# schaltplan.net
KiCad netlist of a schematic drawn in EAGLE
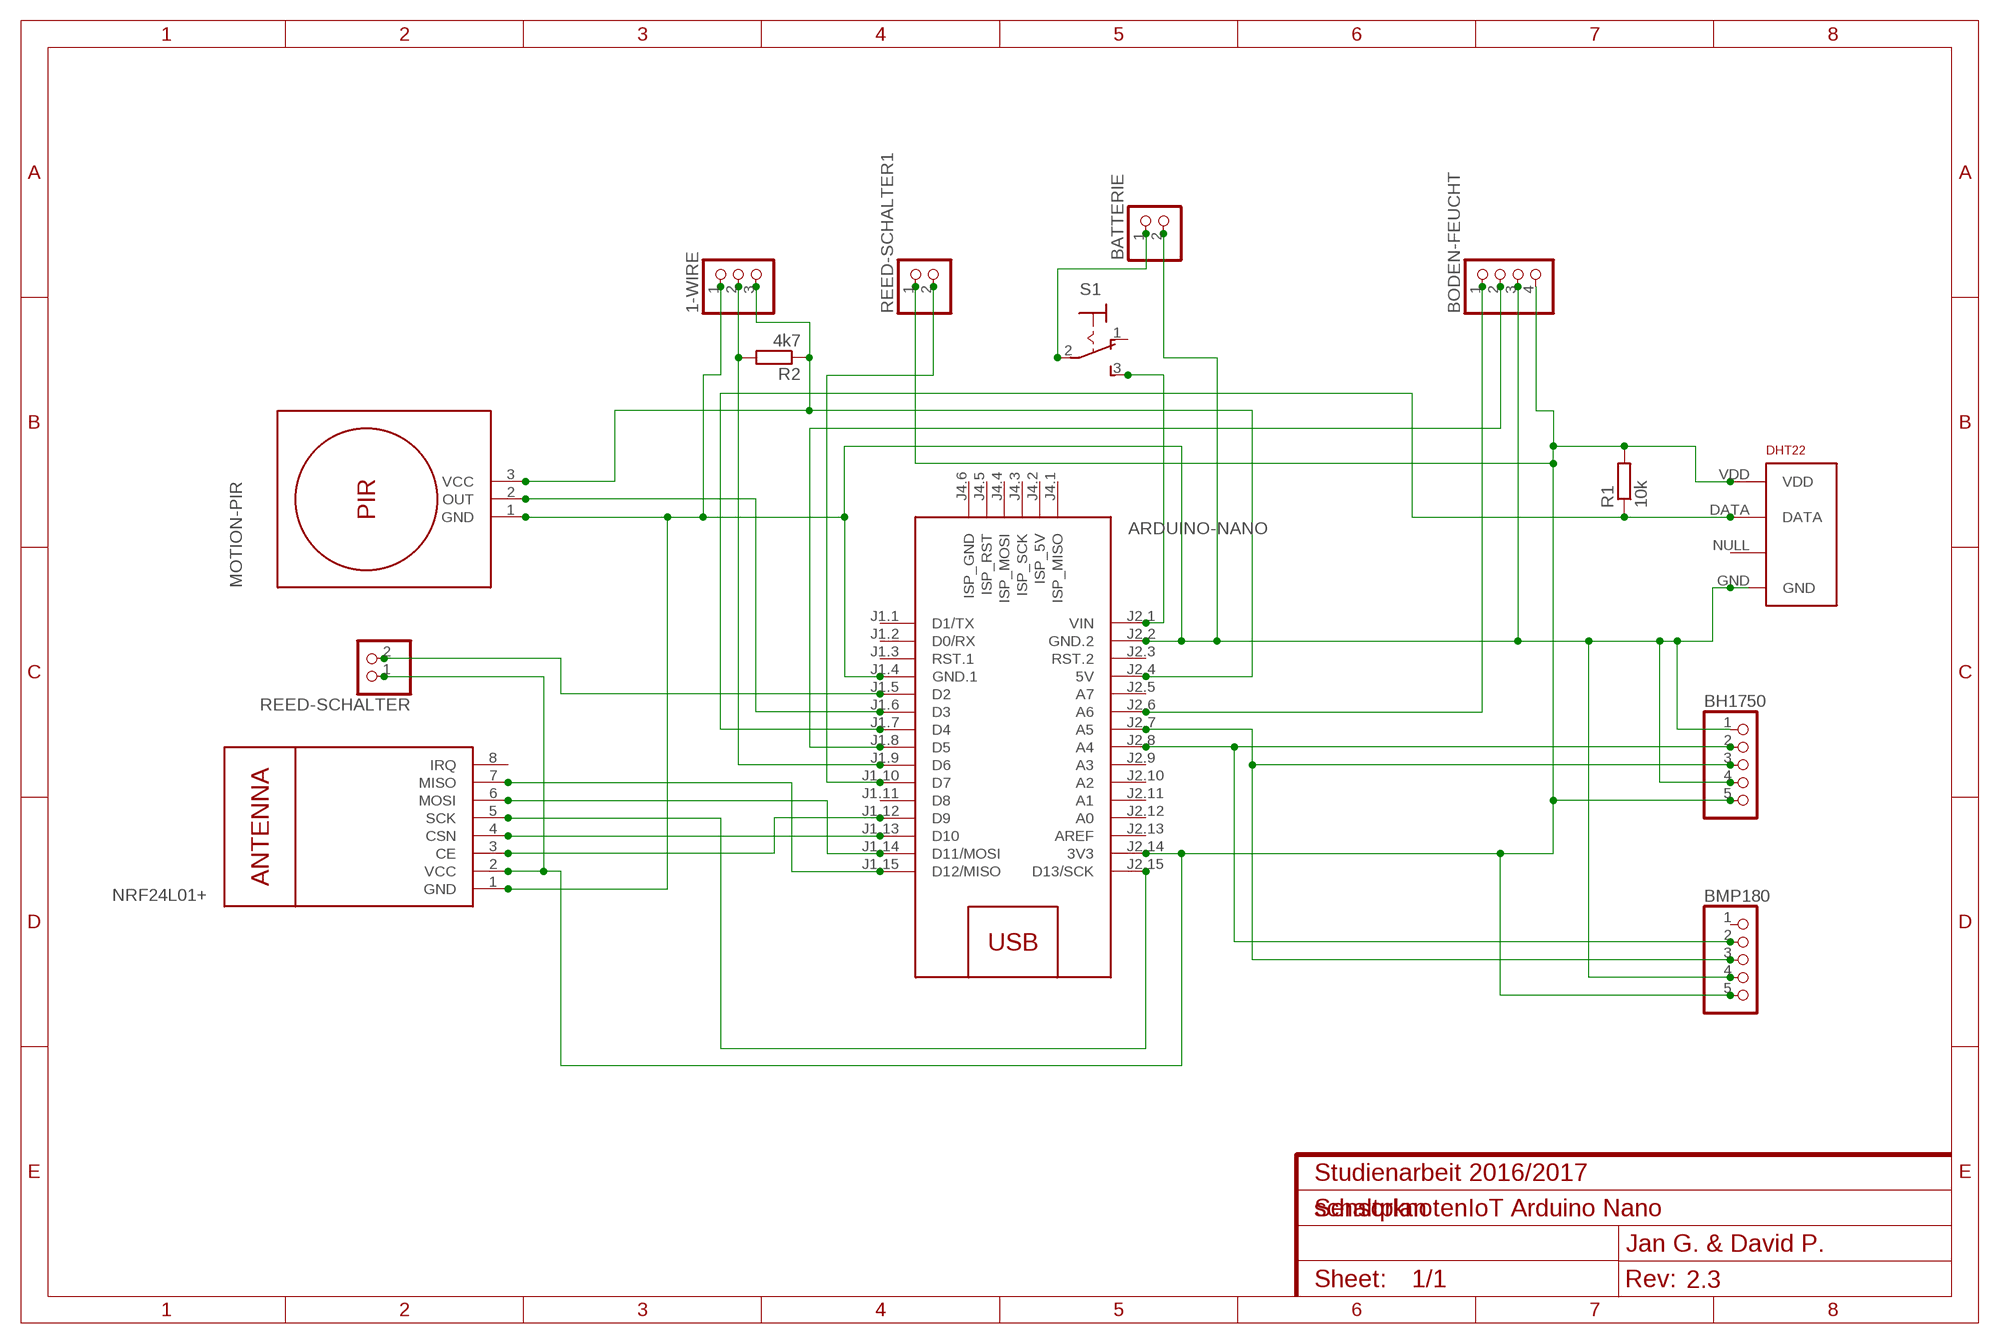
[diagram p0: schematic, sheet 1]

(export (version "E")
  (design (tool "Eeschema 10.0.6"))
  (components
    (comp (ref "1-WIRE")
      (value "PINHD-1X3")
      (footprint "eagle-import:1X03")
      (libsource (lib "eagle-import") (part "PINHD-1X3"))
    )
    (comp (ref "ARDUINO-NANO")
      (value "ARDUINO-NANO-3.0#ISP")
      (footprint "eagle-import:ARDUINO-NANO-3.0#ISP")
      (libsource (lib "eagle-import") (part "ARDUINO-NANO-3.0#ISP"))
    )
    (comp (ref "BATTERIE")
      (value "PINHD-1X2")
      (footprint "eagle-import:1X02")
      (libsource (lib "eagle-import") (part "PINHD-1X2"))
    )
    (comp (ref "BH1750")
      (value "PINHD-1X5")
      (footprint "eagle-import:1X05")
      (libsource (lib "eagle-import") (part "PINHD-1X5"))
    )
    (comp (ref "BMP180")
      (value "PINHD-1X5")
      (footprint "eagle-import:1X05")
      (libsource (lib "eagle-import") (part "PINHD-1X5"))
    )
    (comp (ref "BODEN-FEUCHT")
      (value "PINHD-1X4")
      (footprint "eagle-import:1X04")
      (libsource (lib "eagle-import") (part "PINHD-1X4"))
    )
    (comp (ref "DHT22")
      (value "RHT03_DHT-22_AM2302")
      (footprint "eagle-import:RHT03_DHT-22")
      (libsource (lib "eagle-import") (part "RHT03_DHT-22_AM2302"))
    )
    (comp (ref "MOTION-PIR")
      (value "MOTION-PIR-DYP-ME003")
      (footprint "eagle-import:MOTION-PIR-DYP-ME003")
      (libsource (lib "eagle-import") (part "MOTION-PIR-DYP-ME003"))
    )
    (comp (ref "NRF24L01+")
      (value "WIRELESS-NRF24L01")
      (footprint "eagle-import:WIRELESS-NRF24L01")
      (libsource (lib "eagle-import") (part "WIRELESS-NRF24L01"))
    )
    (comp (ref "R1")
      (value "10k")
      (footprint "eagle-import:0207_10")
      (libsource (lib "eagle-import") (part "R-EU_0207/10"))
    )
    (comp (ref "R2")
      (value "4k7")
      (footprint "eagle-import:0207_10")
      (libsource (lib "eagle-import") (part "R-EU_0207/10"))
    )
    (comp (ref "REED-SCHALTER")
      (value "PINHD-1X2")
      (footprint "eagle-import:1X02")
      (libsource (lib "eagle-import") (part "PINHD-1X2"))
    )
    (comp (ref "REED-SCHALTER1")
      (value "PINHD-1X2")
      (footprint "eagle-import:1X02")
      (libsource (lib "eagle-import") (part "PINHD-1X2"))
    )
    (comp (ref "S1")
      (value "320-916")
      (footprint "eagle-import:320-916")
      (libsource (lib "eagle-import") (part "320-916"))
    )
  )
  (nets
    (net (code "1") (name "Net-(ARDUINO-NANO-3V3)") (class "Default")
      (node (ref "ARDUINO-NANO") (pin "J2.14") (pinfunction "3V3_J2.14") (pintype "power_in"))
      (node (ref "BH1750") (pin "5") (pinfunction "5_5") (pintype "passive"))
      (node (ref "BMP180") (pin "5") (pinfunction "5_5") (pintype "passive"))
      (node (ref "BODEN-FEUCHT") (pin "4") (pinfunction "4_4") (pintype "passive"))
      (node (ref "DHT22") (pin "VDD") (pinfunction "VDD_VDD") (pintype "power_in"))
      (node (ref "NRF24L01+") (pin "2") (pinfunction "VCC_2") (pintype "power_in"))
      (node (ref "R1") (pin "2") (pinfunction "2_2") (pintype "passive"))
      (node (ref "REED-SCHALTER") (pin "1") (pinfunction "1_1") (pintype "passive"))
      (node (ref "REED-SCHALTER1") (pin "1") (pinfunction "1_1") (pintype "passive"))
    )
    (net (code "2") (name "Net-(ARDUINO-NANO-5V)") (class "Default")
      (node (ref "1-WIRE") (pin "3") (pinfunction "3_3") (pintype "passive"))
      (node (ref "ARDUINO-NANO") (pin "J2.4") (pinfunction "5V_J2.4") (pintype "power_in"))
      (node (ref "MOTION-PIR") (pin "3") (pinfunction "VCC_3") (pintype "power_in"))
      (node (ref "R2") (pin "1") (pinfunction "1_1") (pintype "passive"))
    )
    (net (code "3") (name "Net-(ARDUINO-NANO-A4)") (class "Default")
      (node (ref "ARDUINO-NANO") (pin "J2.8") (pinfunction "A4_J2.8") (pintype "bidirectional"))
      (node (ref "BH1750") (pin "2") (pinfunction "2_2") (pintype "passive"))
      (node (ref "BMP180") (pin "2") (pinfunction "2_2") (pintype "passive"))
    )
    (net (code "4") (name "Net-(ARDUINO-NANO-A5)") (class "Default")
      (node (ref "ARDUINO-NANO") (pin "J2.7") (pinfunction "A5_J2.7") (pintype "bidirectional"))
      (node (ref "BH1750") (pin "3") (pinfunction "3_3") (pintype "passive"))
      (node (ref "BMP180") (pin "3") (pinfunction "3_3") (pintype "passive"))
    )
    (net (code "5") (name "Net-(ARDUINO-NANO-A6)") (class "Default")
      (node (ref "ARDUINO-NANO") (pin "J2.6") (pinfunction "A6_J2.6") (pintype "bidirectional"))
      (node (ref "BODEN-FEUCHT") (pin "1") (pinfunction "1_1") (pintype "passive"))
    )
    (net (code "6") (name "Net-(ARDUINO-NANO-D2)") (class "Default")
      (node (ref "ARDUINO-NANO") (pin "J1.5") (pinfunction "D2_J1.5") (pintype "bidirectional"))
      (node (ref "REED-SCHALTER") (pin "2") (pinfunction "2_2") (pintype "passive"))
    )
    (net (code "7") (name "Net-(ARDUINO-NANO-D3)") (class "Default")
      (node (ref "ARDUINO-NANO") (pin "J1.6") (pinfunction "D3_J1.6") (pintype "bidirectional"))
      (node (ref "MOTION-PIR") (pin "2") (pinfunction "OUT_2") (pintype "output"))
    )
    (net (code "8") (name "Net-(ARDUINO-NANO-D4)") (class "Default")
      (node (ref "ARDUINO-NANO") (pin "J1.7") (pinfunction "D4_J1.7") (pintype "bidirectional"))
      (node (ref "DHT22") (pin "DATA") (pinfunction "DATA_DATA") (pintype "bidirectional"))
      (node (ref "R1") (pin "1") (pinfunction "1_1") (pintype "passive"))
    )
    (net (code "9") (name "Net-(ARDUINO-NANO-D5)") (class "Default")
      (node (ref "ARDUINO-NANO") (pin "J1.8") (pinfunction "D5_J1.8") (pintype "bidirectional"))
      (node (ref "BODEN-FEUCHT") (pin "2") (pinfunction "2_2") (pintype "passive"))
    )
    (net (code "10") (name "Net-(ARDUINO-NANO-D6)") (class "Default")
      (node (ref "1-WIRE") (pin "2") (pinfunction "2_2") (pintype "passive"))
      (node (ref "ARDUINO-NANO") (pin "J1.9") (pinfunction "D6_J1.9") (pintype "bidirectional"))
      (node (ref "R2") (pin "2") (pinfunction "2_2") (pintype "passive"))
    )
    (net (code "11") (name "Net-(ARDUINO-NANO-D7)") (class "Default")
      (node (ref "ARDUINO-NANO") (pin "J1.10") (pinfunction "D7_J1.10") (pintype "bidirectional"))
      (node (ref "REED-SCHALTER1") (pin "2") (pinfunction "2_2") (pintype "passive"))
    )
    (net (code "12") (name "Net-(ARDUINO-NANO-D9)") (class "Default")
      (node (ref "ARDUINO-NANO") (pin "J1.12") (pinfunction "D9_J1.12") (pintype "bidirectional"))
      (node (ref "NRF24L01+") (pin "3") (pinfunction "CE_3") (pintype "bidirectional"))
    )
    (net (code "13") (name "Net-(ARDUINO-NANO-D10)") (class "Default")
      (node (ref "ARDUINO-NANO") (pin "J1.13") (pinfunction "D10_J1.13") (pintype "bidirectional"))
      (node (ref "NRF24L01+") (pin "4") (pinfunction "CSN_4") (pintype "bidirectional"))
    )
    (net (code "14") (name "Net-(ARDUINO-NANO-D11{slash}MOSI)") (class "Default")
      (node (ref "ARDUINO-NANO") (pin "J1.14") (pinfunction "D11/MOSI_J1.14") (pintype "bidirectional"))
      (node (ref "NRF24L01+") (pin "6") (pinfunction "MOSI_6") (pintype "bidirectional"))
    )
    (net (code "15") (name "Net-(ARDUINO-NANO-D12{slash}MISO)") (class "Default")
      (node (ref "ARDUINO-NANO") (pin "J1.15") (pinfunction "D12/MISO_J1.15") (pintype "bidirectional"))
      (node (ref "NRF24L01+") (pin "7") (pinfunction "MISO_7") (pintype "bidirectional"))
    )
    (net (code "16") (name "Net-(ARDUINO-NANO-D13{slash}SCK)") (class "Default")
      (node (ref "ARDUINO-NANO") (pin "J2.15") (pinfunction "D13/SCK_J2.15") (pintype "bidirectional"))
      (node (ref "NRF24L01+") (pin "5") (pinfunction "SCK_5") (pintype "bidirectional"))
    )
    (net (code "17") (name "Net-(ARDUINO-NANO-GND.1)") (class "Default")
      (node (ref "1-WIRE") (pin "1") (pinfunction "1_1") (pintype "passive"))
      (node (ref "ARDUINO-NANO") (pin "J1.4") (pinfunction "GND.1_J1.4") (pintype "power_in"))
      (node (ref "ARDUINO-NANO") (pin "J2.2") (pinfunction "GND.2_J2.2") (pintype "power_in"))
      (node (ref "BATTERIE") (pin "2") (pinfunction "2_2") (pintype "passive"))
      (node (ref "BH1750") (pin "1") (pinfunction "1_1") (pintype "passive"))
      (node (ref "BH1750") (pin "4") (pinfunction "4_4") (pintype "passive"))
      (node (ref "BMP180") (pin "4") (pinfunction "4_4") (pintype "passive"))
      (node (ref "BODEN-FEUCHT") (pin "3") (pinfunction "3_3") (pintype "passive"))
      (node (ref "DHT22") (pin "GND") (pinfunction "GND_GND") (pintype "power_in"))
      (node (ref "MOTION-PIR") (pin "1") (pinfunction "GND_1") (pintype "power_in"))
      (node (ref "NRF24L01+") (pin "1") (pinfunction "GND_1") (pintype "power_in"))
    )
    (net (code "18") (name "Net-(ARDUINO-NANO-VIN)") (class "Default")
      (node (ref "ARDUINO-NANO") (pin "J2.1") (pinfunction "VIN_J2.1") (pintype "power_in"))
      (node (ref "S1") (pin "3") (pinfunction "S_3") (pintype "passive"))
    )
    (net (code "19") (name "Net-(S1-P)") (class "Default")
      (node (ref "BATTERIE") (pin "1") (pinfunction "1_1") (pintype "passive"))
      (node (ref "S1") (pin "2") (pinfunction "P_2") (pintype "passive"))
    )
    (net (code "20") (name "unconnected-(ARDUINO-NANO-A0-PadJ2.12)") (class "Default")
      (node (ref "ARDUINO-NANO") (pin "J2.12") (pinfunction "A0_J2.12") (pintype "bidirectional"))
    )
    (net (code "21") (name "unconnected-(ARDUINO-NANO-A1-PadJ2.11)") (class "Default")
      (node (ref "ARDUINO-NANO") (pin "J2.11") (pinfunction "A1_J2.11") (pintype "bidirectional"))
    )
    (net (code "22") (name "unconnected-(ARDUINO-NANO-A2-PadJ2.10)") (class "Default")
      (node (ref "ARDUINO-NANO") (pin "J2.10") (pinfunction "A2_J2.10") (pintype "bidirectional"))
    )
    (net (code "23") (name "unconnected-(ARDUINO-NANO-A3-PadJ2.9)") (class "Default")
      (node (ref "ARDUINO-NANO") (pin "J2.9") (pinfunction "A3_J2.9") (pintype "bidirectional"))
    )
    (net (code "24") (name "unconnected-(ARDUINO-NANO-A7-PadJ2.5)") (class "Default")
      (node (ref "ARDUINO-NANO") (pin "J2.5") (pinfunction "A7_J2.5") (pintype "bidirectional"))
    )
    (net (code "25") (name "unconnected-(ARDUINO-NANO-AREF-PadJ2.13)") (class "Default")
      (node (ref "ARDUINO-NANO") (pin "J2.13") (pinfunction "AREF_J2.13") (pintype "bidirectional"))
    )
    (net (code "26") (name "unconnected-(ARDUINO-NANO-D0{slash}RX-PadJ1.2)") (class "Default")
      (node (ref "ARDUINO-NANO") (pin "J1.2") (pinfunction "D0/RX_J1.2") (pintype "bidirectional"))
    )
    (net (code "27") (name "unconnected-(ARDUINO-NANO-D1{slash}TX-PadJ1.1)") (class "Default")
      (node (ref "ARDUINO-NANO") (pin "J1.1") (pinfunction "D1/TX_J1.1") (pintype "bidirectional"))
    )
    (net (code "28") (name "unconnected-(ARDUINO-NANO-D8-PadJ1.11)") (class "Default")
      (node (ref "ARDUINO-NANO") (pin "J1.11") (pinfunction "D8_J1.11") (pintype "bidirectional"))
    )
    (net (code "29") (name "unconnected-(ARDUINO-NANO-ISP_5V-PadJ4.2)") (class "Default")
      (node (ref "ARDUINO-NANO") (pin "J4.2") (pinfunction "ISP_5V_J4.2") (pintype "bidirectional"))
    )
    (net (code "30") (name "unconnected-(ARDUINO-NANO-ISP_GND-PadJ4.6)") (class "Default")
      (node (ref "ARDUINO-NANO") (pin "J4.6") (pinfunction "ISP_GND_J4.6") (pintype "bidirectional"))
    )
    (net (code "31") (name "unconnected-(ARDUINO-NANO-ISP_MISO-PadJ4.1)") (class "Default")
      (node (ref "ARDUINO-NANO") (pin "J4.1") (pinfunction "ISP_MISO_J4.1") (pintype "bidirectional"))
    )
    (net (code "32") (name "unconnected-(ARDUINO-NANO-ISP_MOSI-PadJ4.4)") (class "Default")
      (node (ref "ARDUINO-NANO") (pin "J4.4") (pinfunction "ISP_MOSI_J4.4") (pintype "bidirectional"))
    )
    (net (code "33") (name "unconnected-(ARDUINO-NANO-ISP_RST-PadJ4.5)") (class "Default")
      (node (ref "ARDUINO-NANO") (pin "J4.5") (pinfunction "ISP_RST_J4.5") (pintype "bidirectional"))
    )
    (net (code "34") (name "unconnected-(ARDUINO-NANO-ISP_SCK-PadJ4.3)") (class "Default")
      (node (ref "ARDUINO-NANO") (pin "J4.3") (pinfunction "ISP_SCK_J4.3") (pintype "bidirectional"))
    )
    (net (code "35") (name "unconnected-(ARDUINO-NANO-RST.1-PadJ1.3)") (class "Default")
      (node (ref "ARDUINO-NANO") (pin "J1.3") (pinfunction "RST.1_J1.3") (pintype "bidirectional"))
    )
    (net (code "36") (name "unconnected-(ARDUINO-NANO-RST.2-PadJ2.3)") (class "Default")
      (node (ref "ARDUINO-NANO") (pin "J2.3") (pinfunction "RST.2_J2.3") (pintype "bidirectional"))
    )
    (net (code "37") (name "unconnected-(BMP180-Pad1)") (class "Default")
      (node (ref "BMP180") (pin "1") (pinfunction "1_1") (pintype "passive"))
    )
    (net (code "38") (name "unconnected-(DHT22-PadNULL)") (class "Default")
      (node (ref "DHT22") (pin "NULL") (pinfunction "NULL_NULL") (pintype "no_connect"))
    )
    (net (code "39") (name "unconnected-(NRF24L01+-IRQ-Pad8)") (class "Default")
      (node (ref "NRF24L01+") (pin "8") (pinfunction "IRQ_8") (pintype "bidirectional"))
    )
    (net (code "40") (name "unconnected-(S1-O-Pad1)") (class "Default")
      (node (ref "S1") (pin "1") (pinfunction "O_1") (pintype "passive"))
    )
  )
)
